# design.net
KiCad netlist of a schematic drawn in EAGLE
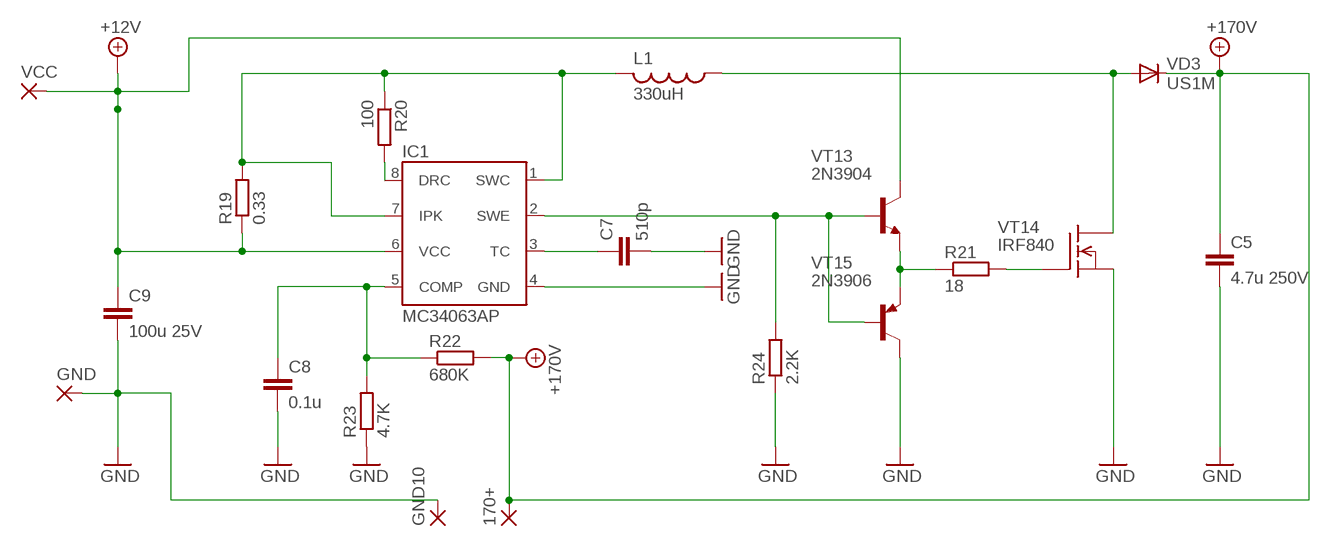
[diagram p0: schematic, sheet 1]

(export (version "E")
  (design (tool "Eeschema 10.0.6"))
  (components
    (comp (ref "170+")
      (value "2,54/0,8")
      (footprint "eagle-import:2,54_0,8")
      (libsource (lib "eagle-import") (part "2,54/0,8"))
    )
    (comp (ref "C5")
      (value "4.7u 250V")
      (footprint "eagle-import:C050-025X075")
      (libsource (lib "eagle-import") (part "C-EU050-025X075"))
    )
    (comp (ref "C7")
      (value "510p")
      (footprint "eagle-import:C050-025X075")
      (libsource (lib "eagle-import") (part "C-EU050-025X075"))
    )
    (comp (ref "C8")
      (value "0.1u")
      (footprint "eagle-import:C050-025X075")
      (libsource (lib "eagle-import") (part "C-EU050-025X075"))
    )
    (comp (ref "C9")
      (value "100u 25V")
      (footprint "eagle-import:C050-025X075")
      (libsource (lib "eagle-import") (part "C-EU050-025X075"))
    )
    (comp (ref "GND")
      (value "2,54/0,8")
      (footprint "eagle-import:2,54_0,8")
      (libsource (lib "eagle-import") (part "2,54/0,8"))
    )
    (comp (ref "GND10")
      (value "2,54/0,8")
      (footprint "eagle-import:2,54_0,8")
      (libsource (lib "eagle-import") (part "2,54/0,8"))
    )
    (comp (ref "IC1")
      (value "MC34063AP")
      (footprint "eagle-import:DIL-08")
      (libsource (lib "eagle-import") (part "MC34063AP"))
    )
    (comp (ref "L1")
      (value "330uH")
      (footprint "eagle-import:0207_10")
      (libsource (lib "eagle-import") (part "L-US0207/10"))
    )
    (comp (ref "R19")
      (value "0.33")
      (footprint "eagle-import:0204_5")
      (libsource (lib "eagle-import") (part "R-EU_0204/5"))
    )
    (comp (ref "R20")
      (value "100")
      (footprint "eagle-import:0204_5")
      (libsource (lib "eagle-import") (part "R-EU_0204/5"))
    )
    (comp (ref "R21")
      (value "18")
      (footprint "eagle-import:0204_5")
      (libsource (lib "eagle-import") (part "R-EU_0204/5"))
    )
    (comp (ref "R22")
      (value "680K")
      (footprint "eagle-import:0204_5")
      (libsource (lib "eagle-import") (part "R-EU_0204/5"))
    )
    (comp (ref "R23")
      (value "4.7K")
      (footprint "eagle-import:0204_5")
      (libsource (lib "eagle-import") (part "R-EU_0204/5"))
    )
    (comp (ref "R24")
      (value "2.2K")
      (footprint "eagle-import:0204_5")
      (libsource (lib "eagle-import") (part "R-EU_0204/5"))
    )
    (comp (ref "VCC")
      (value "2,54/0,8")
      (footprint "eagle-import:2,54_0,8")
      (libsource (lib "eagle-import") (part "2,54/0,8"))
    )
    (comp (ref "VD3")
      (value "US1M")
      (footprint "eagle-import:DO41-10")
      (libsource (lib "eagle-import") (part "1N4004"))
    )
    (comp (ref "VT13")
      (value "2N3904")
      (footprint "eagle-import:TO92")
      (libsource (lib "eagle-import") (part "2N3904"))
    )
    (comp (ref "VT14")
      (value "IRF840")
      (footprint "eagle-import:TO220")
      (libsource (lib "eagle-import") (part "IRF840"))
    )
    (comp (ref "VT15")
      (value "2N3906")
      (footprint "eagle-import:TO92")
      (libsource (lib "eagle-import") (part "2N3906"))
    )
  )
  (nets
    (net (code "1") (name "+12V") (class "Default")
      (node (ref "C9") (pin "1") (pinfunction "1_1") (pintype "passive"))
      (node (ref "IC1") (pin "6") (pinfunction "VCC_6") (pintype "power_in"))
      (node (ref "R19") (pin "1") (pinfunction "1_1") (pintype "passive"))
      (node (ref "VCC") (pin "1") (pinfunction "P_1") (pintype "passive"))
      (node (ref "VT13") (pin "1") (pinfunction "C_1") (pintype "passive"))
    )
    (net (code "2") (name "+170V") (class "Default")
      (node (ref "170+") (pin "1") (pinfunction "P_1") (pintype "passive"))
      (node (ref "C5") (pin "1") (pinfunction "1_1") (pintype "passive"))
      (node (ref "R22") (pin "2") (pinfunction "2_2") (pintype "passive"))
      (node (ref "VD3") (pin "C") (pinfunction "C_C") (pintype "passive"))
    )
    (net (code "3") (name "GND") (class "Default")
      (node (ref "C5") (pin "2") (pinfunction "2_2") (pintype "passive"))
      (node (ref "C7") (pin "2") (pinfunction "2_2") (pintype "passive"))
      (node (ref "C8") (pin "2") (pinfunction "2_2") (pintype "passive"))
      (node (ref "C9") (pin "2") (pinfunction "2_2") (pintype "passive"))
      (node (ref "GND") (pin "1") (pinfunction "P_1") (pintype "passive"))
      (node (ref "GND10") (pin "1") (pinfunction "P_1") (pintype "passive"))
      (node (ref "IC1") (pin "4") (pinfunction "GND_4") (pintype "power_in"))
      (node (ref "R23") (pin "1") (pinfunction "1_1") (pintype "passive"))
      (node (ref "R24") (pin "1") (pinfunction "1_1") (pintype "passive"))
      (node (ref "VT14") (pin "3") (pinfunction "S_3") (pintype "passive"))
      (node (ref "VT15") (pin "1") (pinfunction "C_1") (pintype "passive"))
    )
    (net (code "4") (name "Net-(IC1-COMP)") (class "Default")
      (node (ref "C8") (pin "1") (pinfunction "1_1") (pintype "passive"))
      (node (ref "IC1") (pin "5") (pinfunction "COMP_5") (pintype "input"))
      (node (ref "R22") (pin "1") (pinfunction "1_1") (pintype "passive"))
      (node (ref "R23") (pin "2") (pinfunction "2_2") (pintype "passive"))
    )
    (net (code "5") (name "Net-(IC1-DRC)") (class "Default")
      (node (ref "IC1") (pin "8") (pinfunction "DRC_8") (pintype "input"))
      (node (ref "R20") (pin "2") (pinfunction "2_2") (pintype "passive"))
    )
    (net (code "6") (name "Net-(IC1-IPK)") (class "Default")
      (node (ref "IC1") (pin "1") (pinfunction "SWC_1") (pintype "bidirectional"))
      (node (ref "IC1") (pin "7") (pinfunction "IPK_7") (pintype "input"))
      (node (ref "L1") (pin "2") (pinfunction "2_2") (pintype "passive"))
      (node (ref "R19") (pin "2") (pinfunction "2_2") (pintype "passive"))
      (node (ref "R20") (pin "1") (pinfunction "1_1") (pintype "passive"))
    )
    (net (code "7") (name "Net-(IC1-SWE)") (class "Default")
      (node (ref "IC1") (pin "2") (pinfunction "SWE_2") (pintype "bidirectional"))
      (node (ref "R24") (pin "2") (pinfunction "2_2") (pintype "passive"))
      (node (ref "VT13") (pin "2") (pinfunction "B_2") (pintype "passive"))
      (node (ref "VT15") (pin "2") (pinfunction "B_2") (pintype "passive"))
    )
    (net (code "8") (name "Net-(IC1-TC)") (class "Default")
      (node (ref "C7") (pin "1") (pinfunction "1_1") (pintype "passive"))
      (node (ref "IC1") (pin "3") (pinfunction "TC_3") (pintype "passive"))
    )
    (net (code "9") (name "Net-(VT13-E)") (class "Default")
      (node (ref "R21") (pin "1") (pinfunction "1_1") (pintype "passive"))
      (node (ref "VT13") (pin "3") (pinfunction "E_3") (pintype "passive"))
      (node (ref "VT15") (pin "3") (pinfunction "E_3") (pintype "passive"))
    )
    (net (code "10") (name "Net-(VT14-D)") (class "Default")
      (node (ref "L1") (pin "1") (pinfunction "1_1") (pintype "passive"))
      (node (ref "VD3") (pin "A") (pinfunction "A_A") (pintype "passive"))
      (node (ref "VT14") (pin "2") (pinfunction "D_2") (pintype "passive"))
    )
    (net (code "11") (name "Net-(VT14-G)") (class "Default")
      (node (ref "R21") (pin "2") (pinfunction "2_2") (pintype "passive"))
      (node (ref "VT14") (pin "1") (pinfunction "G_1") (pintype "passive"))
    )
  )
)
